# adc_spi_esp12E.net
KiCad netlist of a schematic drawn in EAGLE
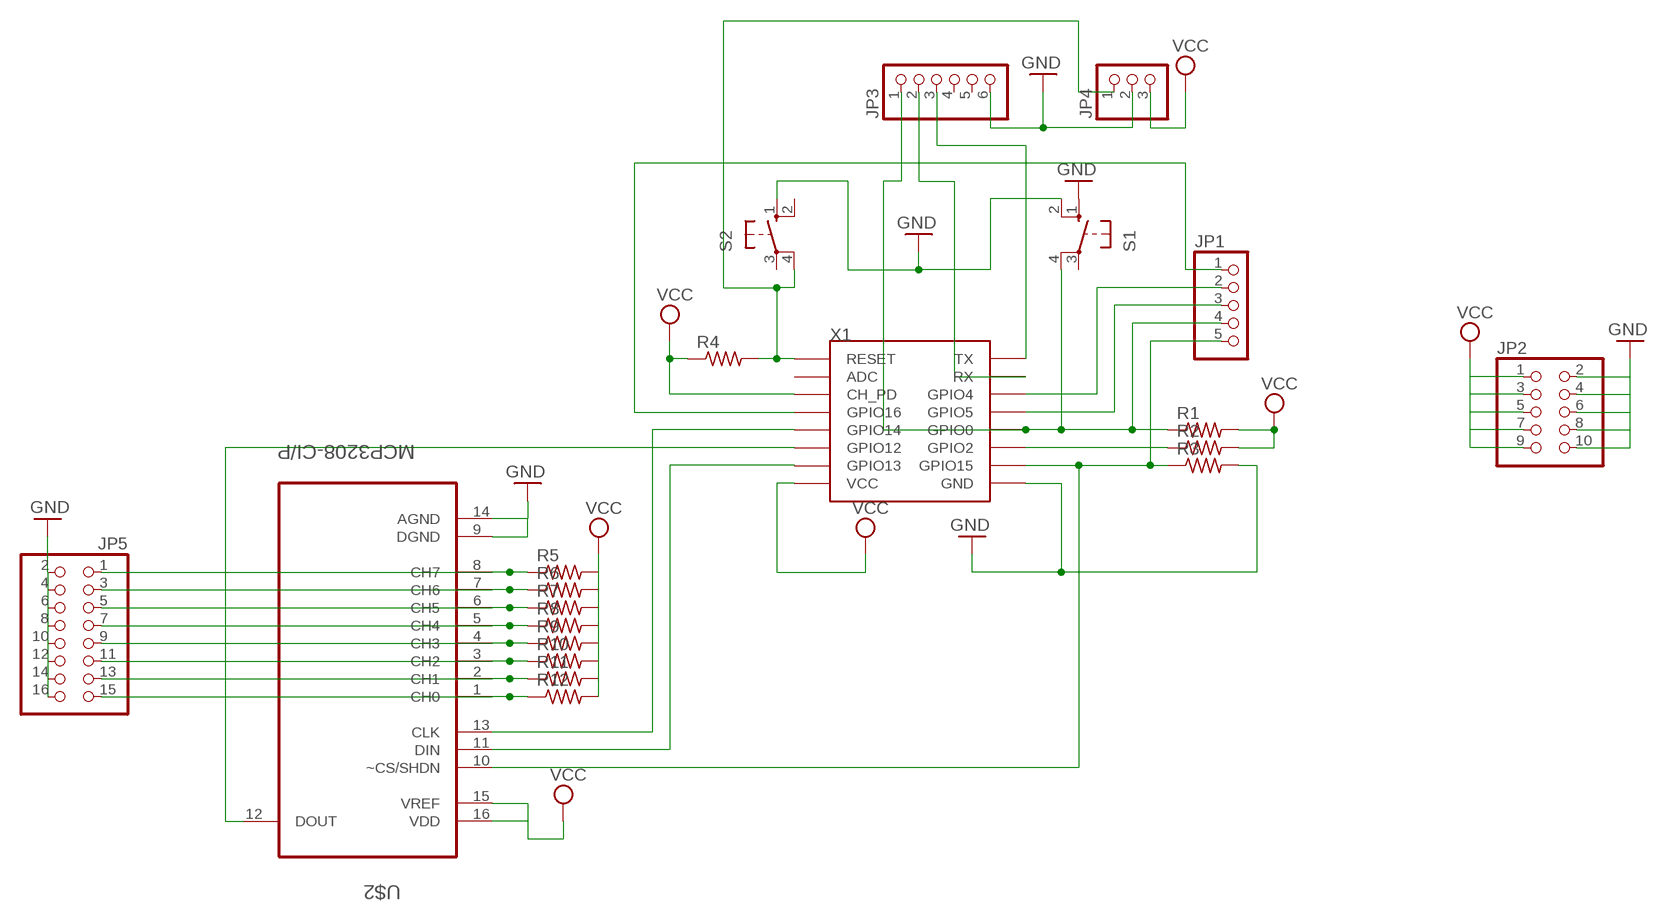
[diagram p0: schematic, sheet 1]

(export (version "E")
  (design (tool "Eeschema 10.0.6"))
  (components
    (comp (ref "JP1")
      (value "PINHD-1X5")
      (footprint "eagle-import:1X05")
      (libsource (lib "eagle-import") (part "PINHD-1X5"))
    )
    (comp (ref "JP2")
      (value "PINHD-2X5")
      (footprint "eagle-import:2X05")
      (libsource (lib "eagle-import") (part "PINHD-2X5"))
    )
    (comp (ref "JP3")
      (value "PINHD-1X6B")
      (footprint "eagle-import:1X06-BIG")
      (libsource (lib "eagle-import") (part "PINHD-1X6B"))
    )
    (comp (ref "JP4")
      (value "PINHD-1X3")
      (footprint "eagle-import:1X03")
      (libsource (lib "eagle-import") (part "PINHD-1X3"))
    )
    (comp (ref "JP5")
      (value "PINHD-2X8")
      (footprint "eagle-import:2X08")
      (libsource (lib "eagle-import") (part "PINHD-2X8"))
    )
    (comp (ref "R1")
      (value "R-US_0204/7")
      (footprint "eagle-import:0204_7")
      (libsource (lib "eagle-import") (part "R-US_0204/7"))
    )
    (comp (ref "R2")
      (value "R-US_0204/7")
      (footprint "eagle-import:0204_7")
      (libsource (lib "eagle-import") (part "R-US_0204/7"))
    )
    (comp (ref "R3")
      (value "R-US_0204/7")
      (footprint "eagle-import:0204_7")
      (libsource (lib "eagle-import") (part "R-US_0204/7"))
    )
    (comp (ref "R4")
      (value "R-US_0204/7")
      (footprint "eagle-import:0204_7")
      (libsource (lib "eagle-import") (part "R-US_0204/7"))
    )
    (comp (ref "R5")
      (value "R-US_0204/7")
      (footprint "eagle-import:0204_7")
      (libsource (lib "eagle-import") (part "R-US_0204/7"))
    )
    (comp (ref "R6")
      (value "R-US_0204/7")
      (footprint "eagle-import:0204_7")
      (libsource (lib "eagle-import") (part "R-US_0204/7"))
    )
    (comp (ref "R7")
      (value "R-US_0204/7")
      (footprint "eagle-import:0204_7")
      (libsource (lib "eagle-import") (part "R-US_0204/7"))
    )
    (comp (ref "R8")
      (value "R-US_0204/7")
      (footprint "eagle-import:0204_7")
      (libsource (lib "eagle-import") (part "R-US_0204/7"))
    )
    (comp (ref "R9")
      (value "R-US_0204/7")
      (footprint "eagle-import:0204_7")
      (libsource (lib "eagle-import") (part "R-US_0204/7"))
    )
    (comp (ref "R10")
      (value "R-US_0204/7")
      (footprint "eagle-import:0204_7")
      (libsource (lib "eagle-import") (part "R-US_0204/7"))
    )
    (comp (ref "R11")
      (value "R-US_0204/7")
      (footprint "eagle-import:0204_7")
      (libsource (lib "eagle-import") (part "R-US_0204/7"))
    )
    (comp (ref "R12")
      (value "R-US_0204/7")
      (footprint "eagle-import:0204_7")
      (libsource (lib "eagle-import") (part "R-US_0204/7"))
    )
    (comp (ref "S1")
      (value "10-XX")
      (footprint "eagle-import:B3F-10XX")
      (fields (field (name "MPN") "B3F-1000"))
      (libsource (lib "eagle-import") (part "10-XX"))
    )
    (comp (ref "S2")
      (value "10-XX")
      (footprint "eagle-import:B3F-10XX")
      (fields (field (name "MPN") "B3F-1000"))
      (libsource (lib "eagle-import") (part "10-XX"))
    )
    (comp (ref "U$2")
      (value "MCP3208-CI/P")
      (footprint "eagle-import:DIP254P762X432-16")
      (fields (field (name "MF") "Microchip"))
      (libsource (lib "eagle-import") (part "MCP3208-CI/P"))
    )
    (comp (ref "X1")
      (value "ESP12SMD")
      (footprint "eagle-import:ESP12-SMD")
      (libsource (lib "eagle-import") (part "ESP12SMD"))
    )
  )
  (nets
    (net (code "1") (name "GND") (class "Default")
      (node (ref "JP2") (pin "10") (pinfunction "10_10") (pintype "passive"))
      (node (ref "JP2") (pin "2") (pinfunction "2_2") (pintype "passive"))
      (node (ref "JP2") (pin "4") (pinfunction "4_4") (pintype "passive"))
      (node (ref "JP2") (pin "6") (pinfunction "6_6") (pintype "passive"))
      (node (ref "JP2") (pin "8") (pinfunction "8_8") (pintype "passive"))
      (node (ref "JP3") (pin "6") (pinfunction "6_6") (pintype "passive"))
      (node (ref "JP4") (pin "2") (pinfunction "2_2") (pintype "passive"))
      (node (ref "JP5") (pin "10") (pinfunction "10_10") (pintype "passive"))
      (node (ref "JP5") (pin "12") (pinfunction "12_12") (pintype "passive"))
      (node (ref "JP5") (pin "14") (pinfunction "14_14") (pintype "passive"))
      (node (ref "JP5") (pin "16") (pinfunction "16_16") (pintype "passive"))
      (node (ref "JP5") (pin "2") (pinfunction "2_2") (pintype "passive"))
      (node (ref "JP5") (pin "4") (pinfunction "4_4") (pintype "passive"))
      (node (ref "JP5") (pin "6") (pinfunction "6_6") (pintype "passive"))
      (node (ref "JP5") (pin "8") (pinfunction "8_8") (pintype "passive"))
      (node (ref "R3") (pin "2") (pinfunction "2_2") (pintype "passive"))
      (node (ref "S1") (pin "1") (pinfunction "S_1") (pintype "passive"))
      (node (ref "S1") (pin "2") (pinfunction "S1_2") (pintype "passive"))
      (node (ref "S2") (pin "1") (pinfunction "S_1") (pintype "passive"))
      (node (ref "U$2") (pin "14") (pinfunction "AGND_14") (pintype "passive"))
      (node (ref "U$2") (pin "9") (pinfunction "DGND_9") (pintype "passive"))
      (node (ref "X1") (pin "GND") (pinfunction "GND_GND") (pintype "bidirectional"))
    )
    (net (code "2") (name "Net-(JP1-Pad1)") (class "Default")
      (node (ref "JP1") (pin "1") (pinfunction "1_1") (pintype "passive"))
      (node (ref "X1") (pin "GPIO16") (pinfunction "GPIO16_GPIO16") (pintype "bidirectional"))
    )
    (net (code "3") (name "Net-(JP1-Pad2)") (class "Default")
      (node (ref "JP1") (pin "2") (pinfunction "2_2") (pintype "passive"))
      (node (ref "X1") (pin "GPIO4") (pinfunction "GPIO4_GPIO4") (pintype "bidirectional"))
    )
    (net (code "4") (name "Net-(JP1-Pad3)") (class "Default")
      (node (ref "JP1") (pin "3") (pinfunction "3_3") (pintype "passive"))
      (node (ref "X1") (pin "GPIO5") (pinfunction "GPIO5_GPIO5") (pintype "bidirectional"))
    )
    (net (code "5") (name "Net-(R2-Pad1)") (class "Default")
      (node (ref "R2") (pin "1") (pinfunction "1_1") (pintype "passive"))
      (node (ref "X1") (pin "GPIO2") (pinfunction "GPIO2_GPIO2") (pintype "bidirectional"))
    )
    (net (code "6") (name "Net-(S1-P1)") (class "Default")
      (node (ref "JP1") (pin "4") (pinfunction "4_4") (pintype "passive"))
      (node (ref "JP3") (pin "1") (pinfunction "1_1") (pintype "passive"))
      (node (ref "R1") (pin "1") (pinfunction "1_1") (pintype "passive"))
      (node (ref "S1") (pin "4") (pinfunction "P1_4") (pintype "passive"))
      (node (ref "X1") (pin "GPIO0") (pinfunction "GPIO0_GPIO0") (pintype "bidirectional"))
    )
    (net (code "7") (name "Net-(S2-P1)") (class "Default")
      (node (ref "JP4") (pin "1") (pinfunction "1_1") (pintype "passive"))
      (node (ref "R4") (pin "2") (pinfunction "2_2") (pintype "passive"))
      (node (ref "S2") (pin "4") (pinfunction "P1_4") (pintype "passive"))
      (node (ref "X1") (pin "RESET") (pinfunction "RESET_RESET") (pintype "bidirectional"))
    )
    (net (code "8") (name "Net-(U$2-CH0)") (class "Default")
      (node (ref "JP5") (pin "15") (pinfunction "15_15") (pintype "passive"))
      (node (ref "R12") (pin "1") (pinfunction "1_1") (pintype "passive"))
      (node (ref "U$2") (pin "1") (pinfunction "CH0_1") (pintype "input"))
    )
    (net (code "9") (name "Net-(U$2-CH1)") (class "Default")
      (node (ref "JP5") (pin "13") (pinfunction "13_13") (pintype "passive"))
      (node (ref "R11") (pin "1") (pinfunction "1_1") (pintype "passive"))
      (node (ref "U$2") (pin "2") (pinfunction "CH1_2") (pintype "input"))
    )
    (net (code "10") (name "Net-(U$2-CH2)") (class "Default")
      (node (ref "JP5") (pin "11") (pinfunction "11_11") (pintype "passive"))
      (node (ref "R10") (pin "1") (pinfunction "1_1") (pintype "passive"))
      (node (ref "U$2") (pin "3") (pinfunction "CH2_3") (pintype "input"))
    )
    (net (code "11") (name "Net-(U$2-CH3)") (class "Default")
      (node (ref "JP5") (pin "9") (pinfunction "9_9") (pintype "passive"))
      (node (ref "R9") (pin "1") (pinfunction "1_1") (pintype "passive"))
      (node (ref "U$2") (pin "4") (pinfunction "CH3_4") (pintype "input"))
    )
    (net (code "12") (name "Net-(U$2-CH4)") (class "Default")
      (node (ref "JP5") (pin "7") (pinfunction "7_7") (pintype "passive"))
      (node (ref "R8") (pin "1") (pinfunction "1_1") (pintype "passive"))
      (node (ref "U$2") (pin "5") (pinfunction "CH4_5") (pintype "input"))
    )
    (net (code "13") (name "Net-(U$2-CH5)") (class "Default")
      (node (ref "JP5") (pin "5") (pinfunction "5_5") (pintype "passive"))
      (node (ref "R7") (pin "1") (pinfunction "1_1") (pintype "passive"))
      (node (ref "U$2") (pin "6") (pinfunction "CH5_6") (pintype "input"))
    )
    (net (code "14") (name "Net-(U$2-CH6)") (class "Default")
      (node (ref "JP5") (pin "3") (pinfunction "3_3") (pintype "passive"))
      (node (ref "R6") (pin "1") (pinfunction "1_1") (pintype "passive"))
      (node (ref "U$2") (pin "7") (pinfunction "CH6_7") (pintype "input"))
    )
    (net (code "15") (name "Net-(U$2-CH7)") (class "Default")
      (node (ref "JP5") (pin "1") (pinfunction "1_1") (pintype "passive"))
      (node (ref "R5") (pin "1") (pinfunction "1_1") (pintype "passive"))
      (node (ref "U$2") (pin "8") (pinfunction "CH7_8") (pintype "input"))
    )
    (net (code "16") (name "Net-(U$2-CLK)") (class "Default")
      (node (ref "U$2") (pin "13") (pinfunction "CLK_13") (pintype "input"))
      (node (ref "X1") (pin "GPIO14") (pinfunction "GPIO14_GPIO14") (pintype "bidirectional"))
    )
    (net (code "17") (name "Net-(U$2-DIN)") (class "Default")
      (node (ref "U$2") (pin "11") (pinfunction "DIN_11") (pintype "input"))
      (node (ref "X1") (pin "GPIO13") (pinfunction "GPIO13_GPIO13") (pintype "bidirectional"))
    )
    (net (code "18") (name "Net-(U$2-DOUT)") (class "Default")
      (node (ref "U$2") (pin "12") (pinfunction "DOUT_12") (pintype "output"))
      (node (ref "X1") (pin "GPIO12") (pinfunction "GPIO12_GPIO12") (pintype "bidirectional"))
    )
    (net (code "19") (name "Net-(U$2-~{CS{slash}SHDN})") (class "Default")
      (node (ref "JP1") (pin "5") (pinfunction "5_5") (pintype "passive"))
      (node (ref "R3") (pin "1") (pinfunction "1_1") (pintype "passive"))
      (node (ref "U$2") (pin "10") (pinfunction "~{CS/SHDN}_10") (pintype "input"))
      (node (ref "X1") (pin "GPIO15") (pinfunction "GPIO15_GPIO15") (pintype "bidirectional"))
    )
    (net (code "20") (name "Net-(X1-RX)") (class "Default")
      (node (ref "JP3") (pin "2") (pinfunction "2_2") (pintype "passive"))
      (node (ref "X1") (pin "RXD0") (pinfunction "RX_RXD0") (pintype "bidirectional"))
    )
    (net (code "21") (name "Net-(X1-TX)") (class "Default")
      (node (ref "JP3") (pin "3") (pinfunction "3_3") (pintype "passive"))
      (node (ref "X1") (pin "TXD0") (pinfunction "TX_TXD0") (pintype "bidirectional"))
    )
    (net (code "22") (name "VCC") (class "Default")
      (node (ref "JP2") (pin "1") (pinfunction "1_1") (pintype "passive"))
      (node (ref "JP2") (pin "3") (pinfunction "3_3") (pintype "passive"))
      (node (ref "JP2") (pin "5") (pinfunction "5_5") (pintype "passive"))
      (node (ref "JP2") (pin "7") (pinfunction "7_7") (pintype "passive"))
      (node (ref "JP2") (pin "9") (pinfunction "9_9") (pintype "passive"))
      (node (ref "JP4") (pin "3") (pinfunction "3_3") (pintype "passive"))
      (node (ref "R1") (pin "2") (pinfunction "2_2") (pintype "passive"))
      (node (ref "R10") (pin "2") (pinfunction "2_2") (pintype "passive"))
      (node (ref "R11") (pin "2") (pinfunction "2_2") (pintype "passive"))
      (node (ref "R12") (pin "2") (pinfunction "2_2") (pintype "passive"))
      (node (ref "R2") (pin "2") (pinfunction "2_2") (pintype "passive"))
      (node (ref "R4") (pin "1") (pinfunction "1_1") (pintype "passive"))
      (node (ref "R5") (pin "2") (pinfunction "2_2") (pintype "passive"))
      (node (ref "R6") (pin "2") (pinfunction "2_2") (pintype "passive"))
      (node (ref "R7") (pin "2") (pinfunction "2_2") (pintype "passive"))
      (node (ref "R8") (pin "2") (pinfunction "2_2") (pintype "passive"))
      (node (ref "R9") (pin "2") (pinfunction "2_2") (pintype "passive"))
      (node (ref "U$2") (pin "15") (pinfunction "VREF_15") (pintype "power_in"))
      (node (ref "U$2") (pin "16") (pinfunction "VDD_16") (pintype "power_in"))
      (node (ref "X1") (pin "CH_PD") (pinfunction "CH_PD_CH_PD") (pintype "bidirectional"))
      (node (ref "X1") (pin "VCC") (pinfunction "VCC_VCC") (pintype "bidirectional"))
    )
    (net (code "23") (name "unconnected-(JP3-Pad4)") (class "Default")
      (node (ref "JP3") (pin "4") (pinfunction "4_4") (pintype "passive"))
    )
    (net (code "24") (name "unconnected-(JP3-Pad5)") (class "Default")
      (node (ref "JP3") (pin "5") (pinfunction "5_5") (pintype "passive"))
    )
    (net (code "25") (name "unconnected-(S1-P-Pad3)") (class "Default")
      (node (ref "S1") (pin "3") (pinfunction "P_3") (pintype "passive"))
    )
    (net (code "26") (name "unconnected-(S2-P-Pad3)") (class "Default")
      (node (ref "S2") (pin "3") (pinfunction "P_3") (pintype "passive"))
    )
    (net (code "27") (name "unconnected-(S2-S1-Pad2)") (class "Default")
      (node (ref "S2") (pin "2") (pinfunction "S1_2") (pintype "passive"))
    )
    (net (code "28") (name "unconnected-(X1-PadADC)") (class "Default")
      (node (ref "X1") (pin "ADC") (pinfunction "ADC_ADC") (pintype "bidirectional"))
    )
  )
)
